# Parola_v1_1.net
KiCad netlist of a schematic drawn in EAGLE
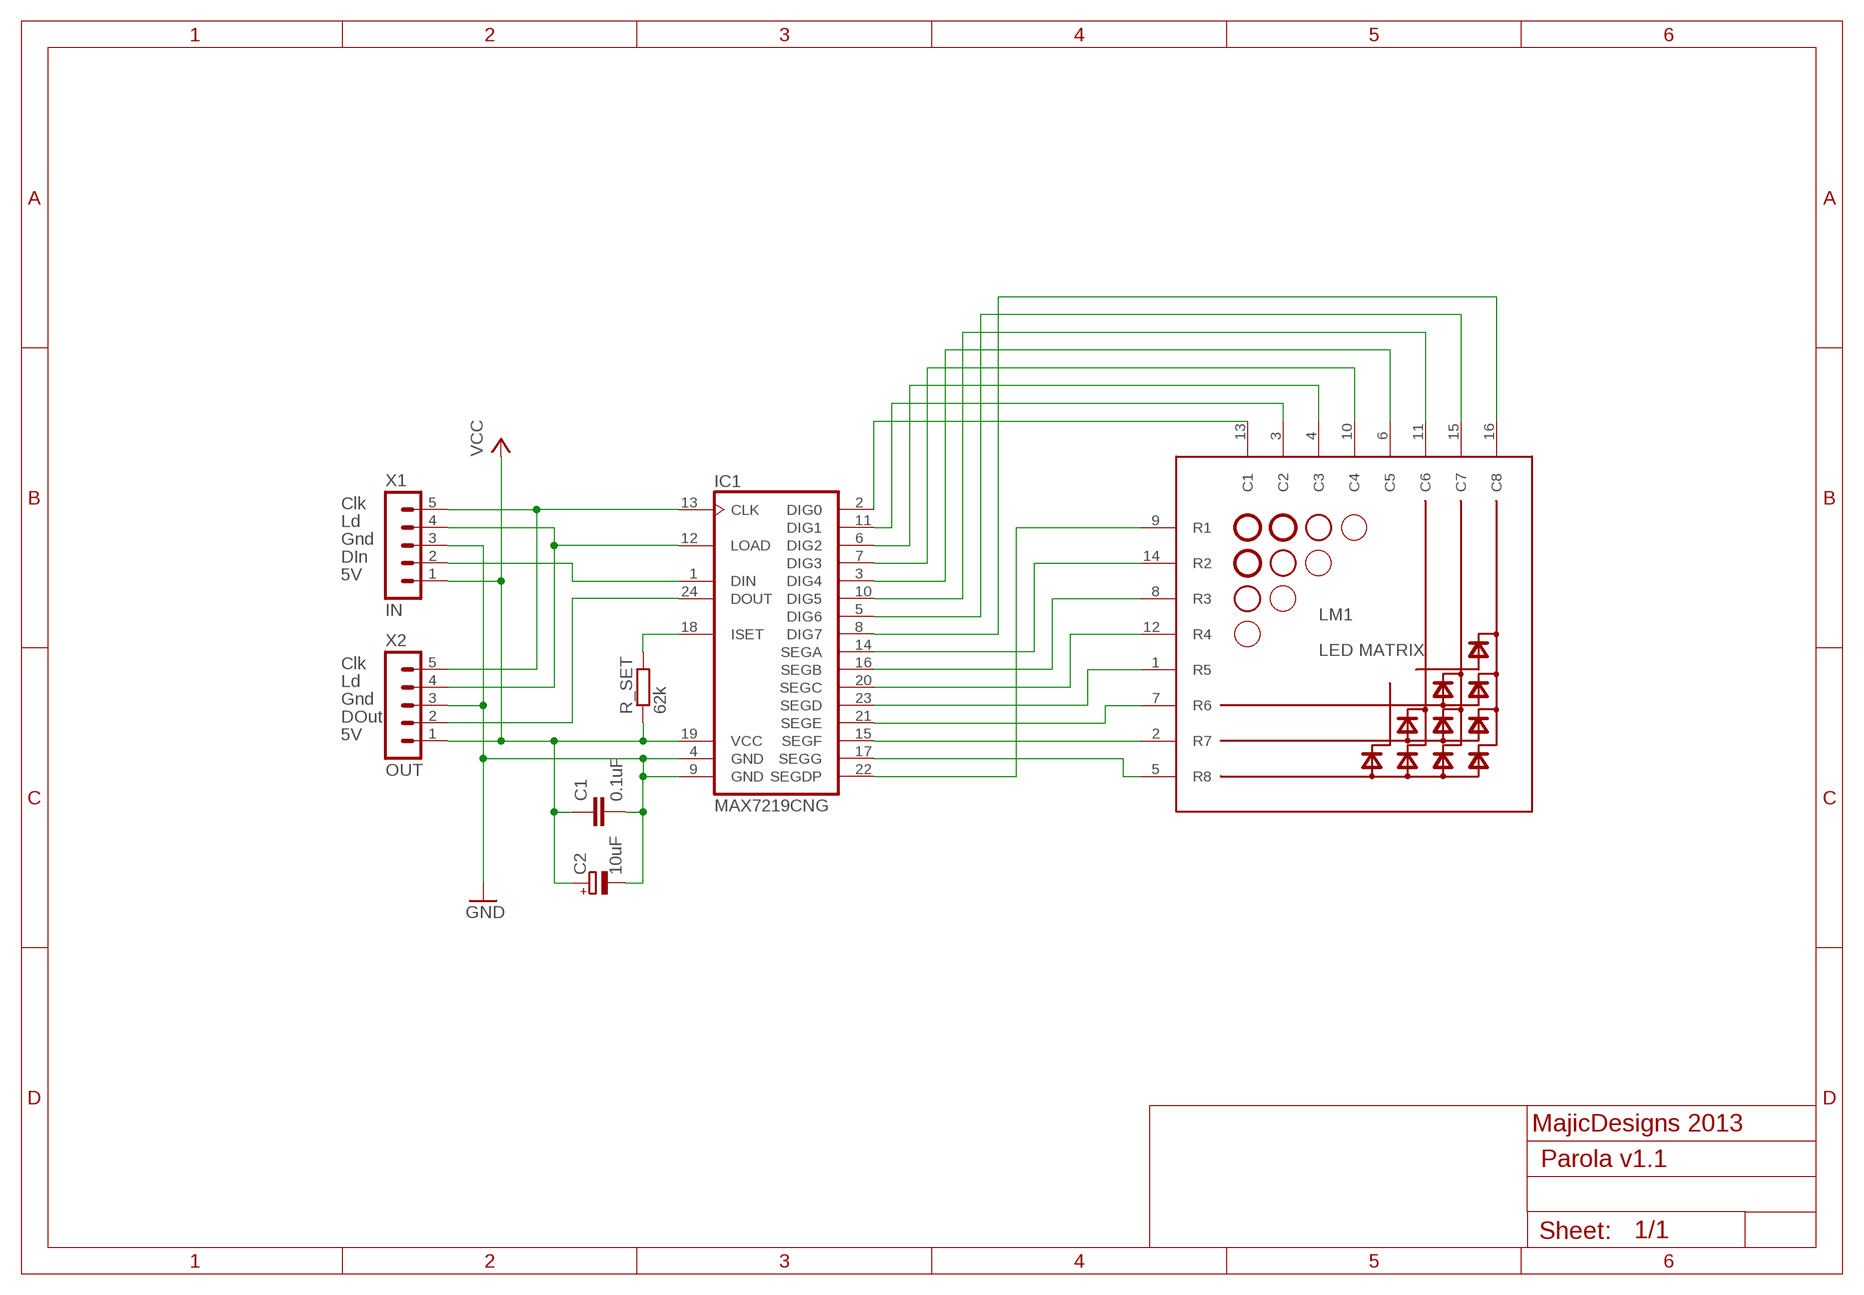
[diagram p0: schematic, sheet 1]

(export (version "E")
  (design (tool "Eeschema 10.0.6"))
  (components
    (comp (ref "C1")
      (value "0.1uF")
      (footprint "eagle-import:C025-024X044")
      (libsource (lib "eagle-import") (part "C-EU025-024X044"))
    )
    (comp (ref "C2")
      (value "10uF")
      (footprint "eagle-import:E2-5")
      (libsource (lib "eagle-import") (part "CPOL-EUE2-5"))
    )
    (comp (ref "IC1")
      (value "MAX7219CNG")
      (footprint "eagle-import:DIL24-3")
      (fields (field (name "MF") "MAXIM"))
      (libsource (lib "eagle-import") (part "MAX7219CNG"))
    )
    (comp (ref "LM1")
      (value "LED MATRIX")
      (footprint "eagle-import:LED_MATRIX")
      (libsource (lib "eagle-import") (part "LD-1088BS_LED_MATRIX"))
    )
    (comp (ref "R_SET")
      (value "62k")
      (footprint "eagle-import:0207_10")
      (libsource (lib "eagle-import") (part "R-EU_0207/10"))
    )
    (comp (ref "X1")
      (value "IN")
      (footprint "eagle-import:MAR05-1")
      (libsource (lib "eagle-import") (part "MAR05-1"))
    )
    (comp (ref "X2")
      (value "OUT")
      (footprint "eagle-import:MAR05-1")
      (libsource (lib "eagle-import") (part "MAR05-1"))
    )
  )
  (nets
    (net (code "1") (name "GND") (class "Default")
      (node (ref "C1") (pin "2") (pinfunction "2_2") (pintype "passive"))
      (node (ref "C2") (pin "-") (pinfunction "-_-") (pintype "passive"))
      (node (ref "IC1") (pin "4") (pinfunction "GND_4") (pintype "power_in"))
      (node (ref "IC1") (pin "9") (pinfunction "GND_9") (pintype "power_in"))
      (node (ref "X1") (pin "3") (pinfunction "3_3") (pintype "passive"))
      (node (ref "X2") (pin "3") (pinfunction "3_3") (pintype "passive"))
    )
    (net (code "2") (name "Net-(IC1-CLK)") (class "Default")
      (node (ref "IC1") (pin "13") (pinfunction "CLK_13") (pintype "input"))
      (node (ref "X1") (pin "5") (pinfunction "5_5") (pintype "passive"))
      (node (ref "X2") (pin "5") (pinfunction "5_5") (pintype "passive"))
    )
    (net (code "3") (name "Net-(IC1-DIG0)") (class "Default")
      (node (ref "IC1") (pin "2") (pinfunction "DIG0_2") (pintype "output"))
      (node (ref "LM1") (pin "13") (pinfunction "C1_13") (pintype "input"))
    )
    (net (code "4") (name "Net-(IC1-DIG1)") (class "Default")
      (node (ref "IC1") (pin "11") (pinfunction "DIG1_11") (pintype "output"))
      (node (ref "LM1") (pin "3") (pinfunction "C2_3") (pintype "input"))
    )
    (net (code "5") (name "Net-(IC1-DIG2)") (class "Default")
      (node (ref "IC1") (pin "6") (pinfunction "DIG2_6") (pintype "output"))
      (node (ref "LM1") (pin "4") (pinfunction "C3_4") (pintype "input"))
    )
    (net (code "6") (name "Net-(IC1-DIG3)") (class "Default")
      (node (ref "IC1") (pin "7") (pinfunction "DIG3_7") (pintype "output"))
      (node (ref "LM1") (pin "10") (pinfunction "C4_10") (pintype "input"))
    )
    (net (code "7") (name "Net-(IC1-DIG4)") (class "Default")
      (node (ref "IC1") (pin "3") (pinfunction "DIG4_3") (pintype "output"))
      (node (ref "LM1") (pin "6") (pinfunction "C5_6") (pintype "input"))
    )
    (net (code "8") (name "Net-(IC1-DIG5)") (class "Default")
      (node (ref "IC1") (pin "10") (pinfunction "DIG5_10") (pintype "output"))
      (node (ref "LM1") (pin "11") (pinfunction "C6_11") (pintype "input"))
    )
    (net (code "9") (name "Net-(IC1-DIG6)") (class "Default")
      (node (ref "IC1") (pin "5") (pinfunction "DIG6_5") (pintype "output"))
      (node (ref "LM1") (pin "15") (pinfunction "C7_15") (pintype "input"))
    )
    (net (code "10") (name "Net-(IC1-DIG7)") (class "Default")
      (node (ref "IC1") (pin "8") (pinfunction "DIG7_8") (pintype "output"))
      (node (ref "LM1") (pin "16") (pinfunction "C8_16") (pintype "input"))
    )
    (net (code "11") (name "Net-(IC1-DIN)") (class "Default")
      (node (ref "IC1") (pin "1") (pinfunction "DIN_1") (pintype "input"))
      (node (ref "X1") (pin "2") (pinfunction "2_2") (pintype "passive"))
    )
    (net (code "12") (name "Net-(IC1-DOUT)") (class "Default")
      (node (ref "IC1") (pin "24") (pinfunction "DOUT_24") (pintype "output"))
      (node (ref "X2") (pin "2") (pinfunction "2_2") (pintype "passive"))
    )
    (net (code "13") (name "Net-(IC1-ISET)") (class "Default")
      (node (ref "IC1") (pin "18") (pinfunction "ISET_18") (pintype "input"))
      (node (ref "R_SET") (pin "2") (pinfunction "2_2") (pintype "passive"))
    )
    (net (code "14") (name "Net-(IC1-LOAD)") (class "Default")
      (node (ref "IC1") (pin "12") (pinfunction "LOAD_12") (pintype "input"))
      (node (ref "X1") (pin "4") (pinfunction "4_4") (pintype "passive"))
      (node (ref "X2") (pin "4") (pinfunction "4_4") (pintype "passive"))
    )
    (net (code "15") (name "Net-(IC1-SEGA)") (class "Default")
      (node (ref "IC1") (pin "14") (pinfunction "SEGA_14") (pintype "output"))
      (node (ref "LM1") (pin "14") (pinfunction "R2_14") (pintype "input"))
    )
    (net (code "16") (name "Net-(IC1-SEGB)") (class "Default")
      (node (ref "IC1") (pin "16") (pinfunction "SEGB_16") (pintype "output"))
      (node (ref "LM1") (pin "8") (pinfunction "R3_8") (pintype "input"))
    )
    (net (code "17") (name "Net-(IC1-SEGC)") (class "Default")
      (node (ref "IC1") (pin "20") (pinfunction "SEGC_20") (pintype "output"))
      (node (ref "LM1") (pin "12") (pinfunction "R4_12") (pintype "input"))
    )
    (net (code "18") (name "Net-(IC1-SEGD)") (class "Default")
      (node (ref "IC1") (pin "23") (pinfunction "SEGD_23") (pintype "output"))
      (node (ref "LM1") (pin "1") (pinfunction "R5_1") (pintype "input"))
    )
    (net (code "19") (name "Net-(IC1-SEGDP)") (class "Default")
      (node (ref "IC1") (pin "22") (pinfunction "SEGDP_22") (pintype "output"))
      (node (ref "LM1") (pin "9") (pinfunction "R1_9") (pintype "input"))
    )
    (net (code "20") (name "Net-(IC1-SEGE)") (class "Default")
      (node (ref "IC1") (pin "21") (pinfunction "SEGE_21") (pintype "output"))
      (node (ref "LM1") (pin "7") (pinfunction "R6_7") (pintype "input"))
    )
    (net (code "21") (name "Net-(IC1-SEGF)") (class "Default")
      (node (ref "IC1") (pin "15") (pinfunction "SEGF_15") (pintype "output"))
      (node (ref "LM1") (pin "2") (pinfunction "R7_2") (pintype "input"))
    )
    (net (code "22") (name "Net-(IC1-SEGG)") (class "Default")
      (node (ref "IC1") (pin "17") (pinfunction "SEGG_17") (pintype "output"))
      (node (ref "LM1") (pin "5") (pinfunction "R8_5") (pintype "input"))
    )
    (net (code "23") (name "VCC") (class "Default")
      (node (ref "C1") (pin "1") (pinfunction "1_1") (pintype "passive"))
      (node (ref "C2") (pin "+") (pinfunction "+_+") (pintype "passive"))
      (node (ref "IC1") (pin "19") (pinfunction "VCC_19") (pintype "power_in"))
      (node (ref "R_SET") (pin "1") (pinfunction "1_1") (pintype "passive"))
      (node (ref "X1") (pin "1") (pinfunction "1_1") (pintype "passive"))
      (node (ref "X2") (pin "1") (pinfunction "1_1") (pintype "passive"))
    )
  )
)
